# transmitter.net
KiCad netlist of a schematic drawn in EAGLE
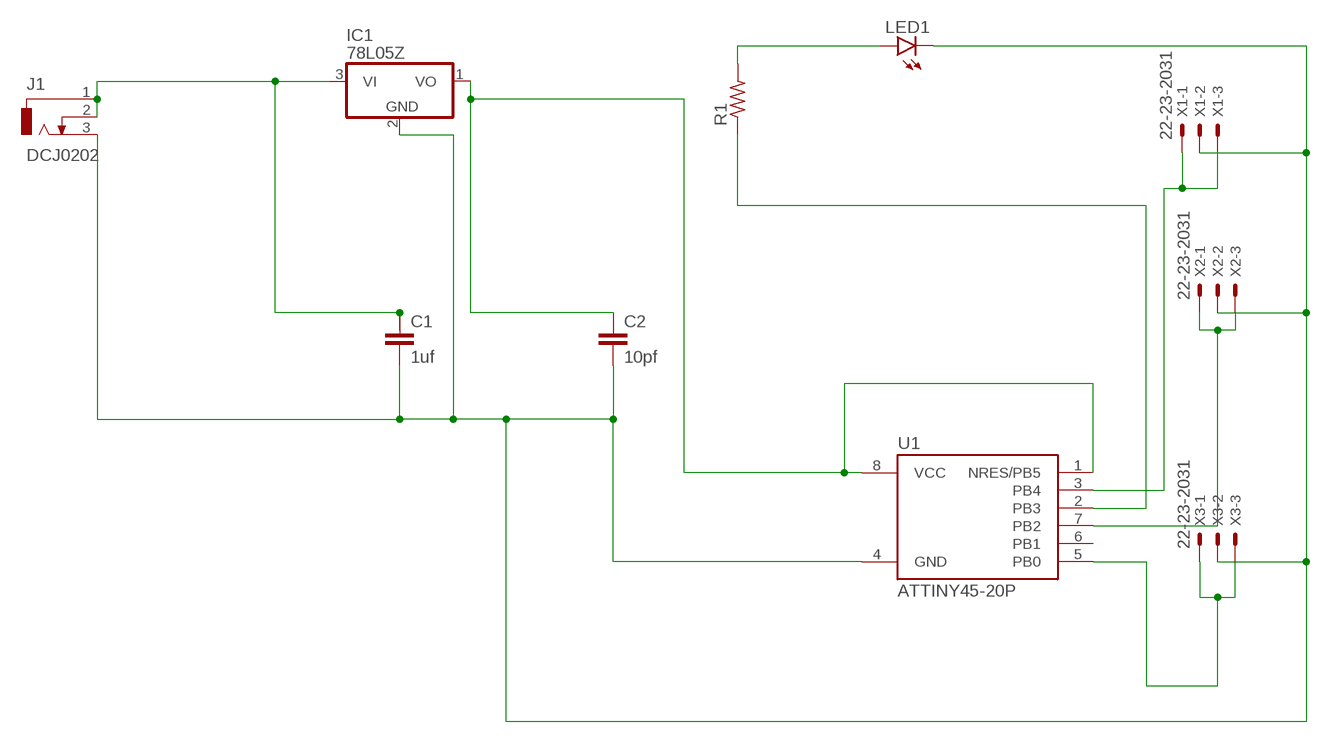
[diagram p0: schematic, sheet 1]

(export (version "E")
  (design (tool "Eeschema 10.0.6"))
  (components
    (comp (ref "C1")
      (value "1uf")
      (footprint "eagle-import:C2.5-2")
      (libsource (lib "eagle-import") (part "C2.5/2"))
    )
    (comp (ref "C2")
      (value "10pf")
      (footprint "eagle-import:C2.5-2")
      (libsource (lib "eagle-import") (part "C2.5/2"))
    )
    (comp (ref "IC1")
      (value "78L05Z")
      (footprint "eagle-import:TO92")
      (libsource (lib "eagle-import") (part "78ZL05"))
    )
    (comp (ref "J1")
      (value "DCJ0202")
      (footprint "eagle-import:DCJ0202")
      (libsource (lib "eagle-import") (part "DCJ0202"))
    )
    (comp (ref "LED1")
      (value "LED3MM")
      (footprint "eagle-import:LED3MM")
      (libsource (lib "eagle-import") (part "LED3MM"))
    )
    (comp (ref "R1")
      (value "R-US_0207/10")
      (footprint "eagle-import:0207_10")
      (libsource (lib "eagle-import") (part "R-US_0207/10"))
    )
    (comp (ref "U1")
      (value "ATTINY45-20P")
      (footprint "eagle-import:PDIP08_300MIL")
      (libsource (lib "eagle-import") (part "ATTINY45P-20"))
    )
    (comp (ref "X1")
      (value "22-23-2031")
      (footprint "eagle-import:22-23-2031")
      (fields (field (name "MF") "MOLEX"))
      (libsource (lib "eagle-import") (part "22-23-2031"))
    )
    (comp (ref "X2")
      (value "22-23-2031")
      (footprint "eagle-import:22-23-2031")
      (fields (field (name "MF") "MOLEX"))
      (libsource (lib "eagle-import") (part "22-23-2031"))
    )
    (comp (ref "X3")
      (value "22-23-2031")
      (footprint "eagle-import:22-23-2031")
      (fields (field (name "MF") "MOLEX"))
      (libsource (lib "eagle-import") (part "22-23-2031"))
    )
  )
  (nets
    (net (code "1") (name "Net-(IC1-GND)") (class "Default")
      (node (ref "C1") (pin "2") (pinfunction "2_2") (pintype "passive"))
      (node (ref "C2") (pin "2") (pinfunction "2_2") (pintype "passive"))
      (node (ref "IC1") (pin "2") (pinfunction "GND_2") (pintype "passive"))
      (node (ref "J1") (pin "3") (pinfunction "3_3") (pintype "passive"))
      (node (ref "LED1") (pin "K") (pinfunction "C_K") (pintype "passive"))
      (node (ref "U1") (pin "4") (pinfunction "GND_4") (pintype "power_in"))
      (node (ref "X1") (pin "2") (pinfunction "S_2") (pintype "passive"))
      (node (ref "X2") (pin "2") (pinfunction "S_2") (pintype "passive"))
      (node (ref "X3") (pin "2") (pinfunction "S_2") (pintype "passive"))
    )
    (net (code "2") (name "Net-(IC1-VI)") (class "Default")
      (node (ref "C1") (pin "1") (pinfunction "1_1") (pintype "passive"))
      (node (ref "IC1") (pin "3") (pinfunction "VI_3") (pintype "input"))
      (node (ref "J1") (pin "1") (pinfunction "1_1") (pintype "passive"))
      (node (ref "J1") (pin "2") (pinfunction "2_2") (pintype "passive"))
    )
    (net (code "3") (name "Net-(IC1-VO)") (class "Default")
      (node (ref "C2") (pin "1") (pinfunction "1_1") (pintype "passive"))
      (node (ref "IC1") (pin "1") (pinfunction "VO_1") (pintype "passive"))
      (node (ref "U1") (pin "1") (pinfunction "NRES/PB5_1") (pintype "bidirectional"))
      (node (ref "U1") (pin "8") (pinfunction "VCC_8") (pintype "power_in"))
    )
    (net (code "4") (name "Net-(LED1-PadA)") (class "Default")
      (node (ref "LED1") (pin "A") (pinfunction "A_A") (pintype "passive"))
      (node (ref "R1") (pin "2") (pinfunction "2_2") (pintype "passive"))
    )
    (net (code "5") (name "Net-(U1-PB0)") (class "Default")
      (node (ref "U1") (pin "5") (pinfunction "PB0_5") (pintype "bidirectional"))
      (node (ref "X3") (pin "1") (pinfunction "S_1") (pintype "passive"))
      (node (ref "X3") (pin "3") (pinfunction "S_3") (pintype "passive"))
    )
    (net (code "6") (name "Net-(U1-PB2)") (class "Default")
      (node (ref "U1") (pin "7") (pinfunction "PB2_7") (pintype "bidirectional"))
      (node (ref "X2") (pin "1") (pinfunction "S_1") (pintype "passive"))
      (node (ref "X2") (pin "3") (pinfunction "S_3") (pintype "passive"))
    )
    (net (code "7") (name "Net-(U1-PB3)") (class "Default")
      (node (ref "R1") (pin "1") (pinfunction "1_1") (pintype "passive"))
      (node (ref "U1") (pin "2") (pinfunction "PB3_2") (pintype "bidirectional"))
    )
    (net (code "8") (name "Net-(U1-PB4)") (class "Default")
      (node (ref "U1") (pin "3") (pinfunction "PB4_3") (pintype "bidirectional"))
      (node (ref "X1") (pin "1") (pinfunction "S_1") (pintype "passive"))
      (node (ref "X1") (pin "3") (pinfunction "S_3") (pintype "passive"))
    )
    (net (code "9") (name "unconnected-(U1-PB1-Pad6)") (class "Default")
      (node (ref "U1") (pin "6") (pinfunction "PB1_6") (pintype "bidirectional"))
    )
  )
)
